# Push_function.net
KiCad netlist of a schematic drawn in Altium Designer
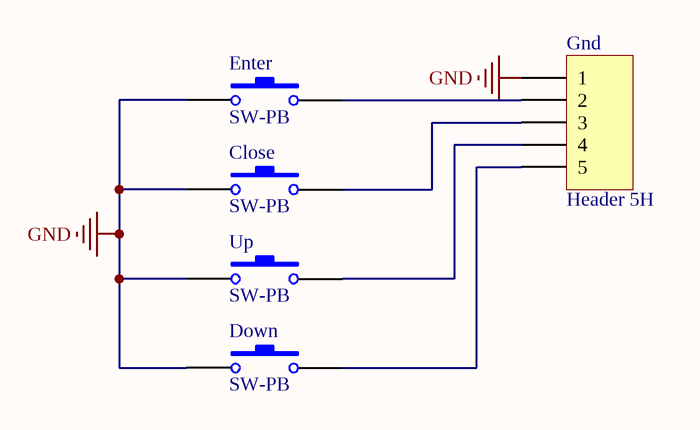
[diagram p0: Push function.SchDoc]

(export (version "E")
  (design (tool "Eeschema 10.0.6"))
  (components
    (comp (ref "Close")
      (value "SW-PB")
      (footprint "SPST-2")
      (description "Switch")
      (fields (field (name "PUBLISHER") "Altium Limited"))
      (libsource (lib "Miscellaneous Devices") (part "SW-PB"))
    )
    (comp (ref "Down")
      (value "SW-PB")
      (footprint "SPST-2")
      (description "Switch")
      (fields (field (name "PUBLISHER") "Altium Limited"))
      (libsource (lib "Miscellaneous Devices") (part "SW-PB"))
    )
    (comp (ref "Enter")
      (value "SW-PB")
      (footprint "SPST-2")
      (description "Switch")
      (fields (field (name "PUBLISHER") "Altium Limited"))
      (libsource (lib "Miscellaneous Devices") (part "SW-PB"))
    )
    (comp (ref "Gnd")
      (value "Header 5H")
      (footprint "HDR1X5H")
      (description "Header, 5-Pin, Right Angle")
      (fields (field (name "PUBLISHER") "Altium Limited"))
      (libsource (lib "Miscellaneous Connectors") (part "Header 5H"))
    )
    (comp (ref "Up")
      (value "SW-PB")
      (footprint "SPST-2")
      (description "Switch")
      (fields (field (name "PUBLISHER") "Altium Limited"))
      (libsource (lib "Miscellaneous Devices") (part "SW-PB"))
    )
  )
  (nets
    (net (code "1") (name "GND") (class "Default")
      (node (ref "Close") (pin "1") (pinfunction "1_1") (pintype "passive"))
      (node (ref "Down") (pin "1") (pinfunction "1_1") (pintype "passive"))
      (node (ref "Enter") (pin "1") (pinfunction "1_1") (pintype "passive"))
      (node (ref "Gnd") (pin "1") (pinfunction "1_1") (pintype "passive"))
      (node (ref "Up") (pin "1") (pinfunction "1_1") (pintype "passive"))
    )
    (net (code "2") (name "Net-(Close-Pad2)") (class "Default")
      (node (ref "Close") (pin "2") (pinfunction "2_2") (pintype "passive"))
      (node (ref "Gnd") (pin "3") (pinfunction "3_3") (pintype "passive"))
    )
    (net (code "3") (name "Net-(Down-Pad2)") (class "Default")
      (node (ref "Down") (pin "2") (pinfunction "2_2") (pintype "passive"))
      (node (ref "Gnd") (pin "5") (pinfunction "5_5") (pintype "passive"))
    )
    (net (code "4") (name "Net-(Enter-Pad2)") (class "Default")
      (node (ref "Enter") (pin "2") (pinfunction "2_2") (pintype "passive"))
      (node (ref "Gnd") (pin "2") (pinfunction "2_2") (pintype "passive"))
    )
    (net (code "5") (name "Net-(Gnd-Pad4)") (class "Default")
      (node (ref "Gnd") (pin "4") (pinfunction "4_4") (pintype "passive"))
      (node (ref "Up") (pin "2") (pinfunction "2_2") (pintype "passive"))
    )
  )
)
